# Test_Jig_Project.net
KiCad netlist of a schematic drawn in Altium Designer
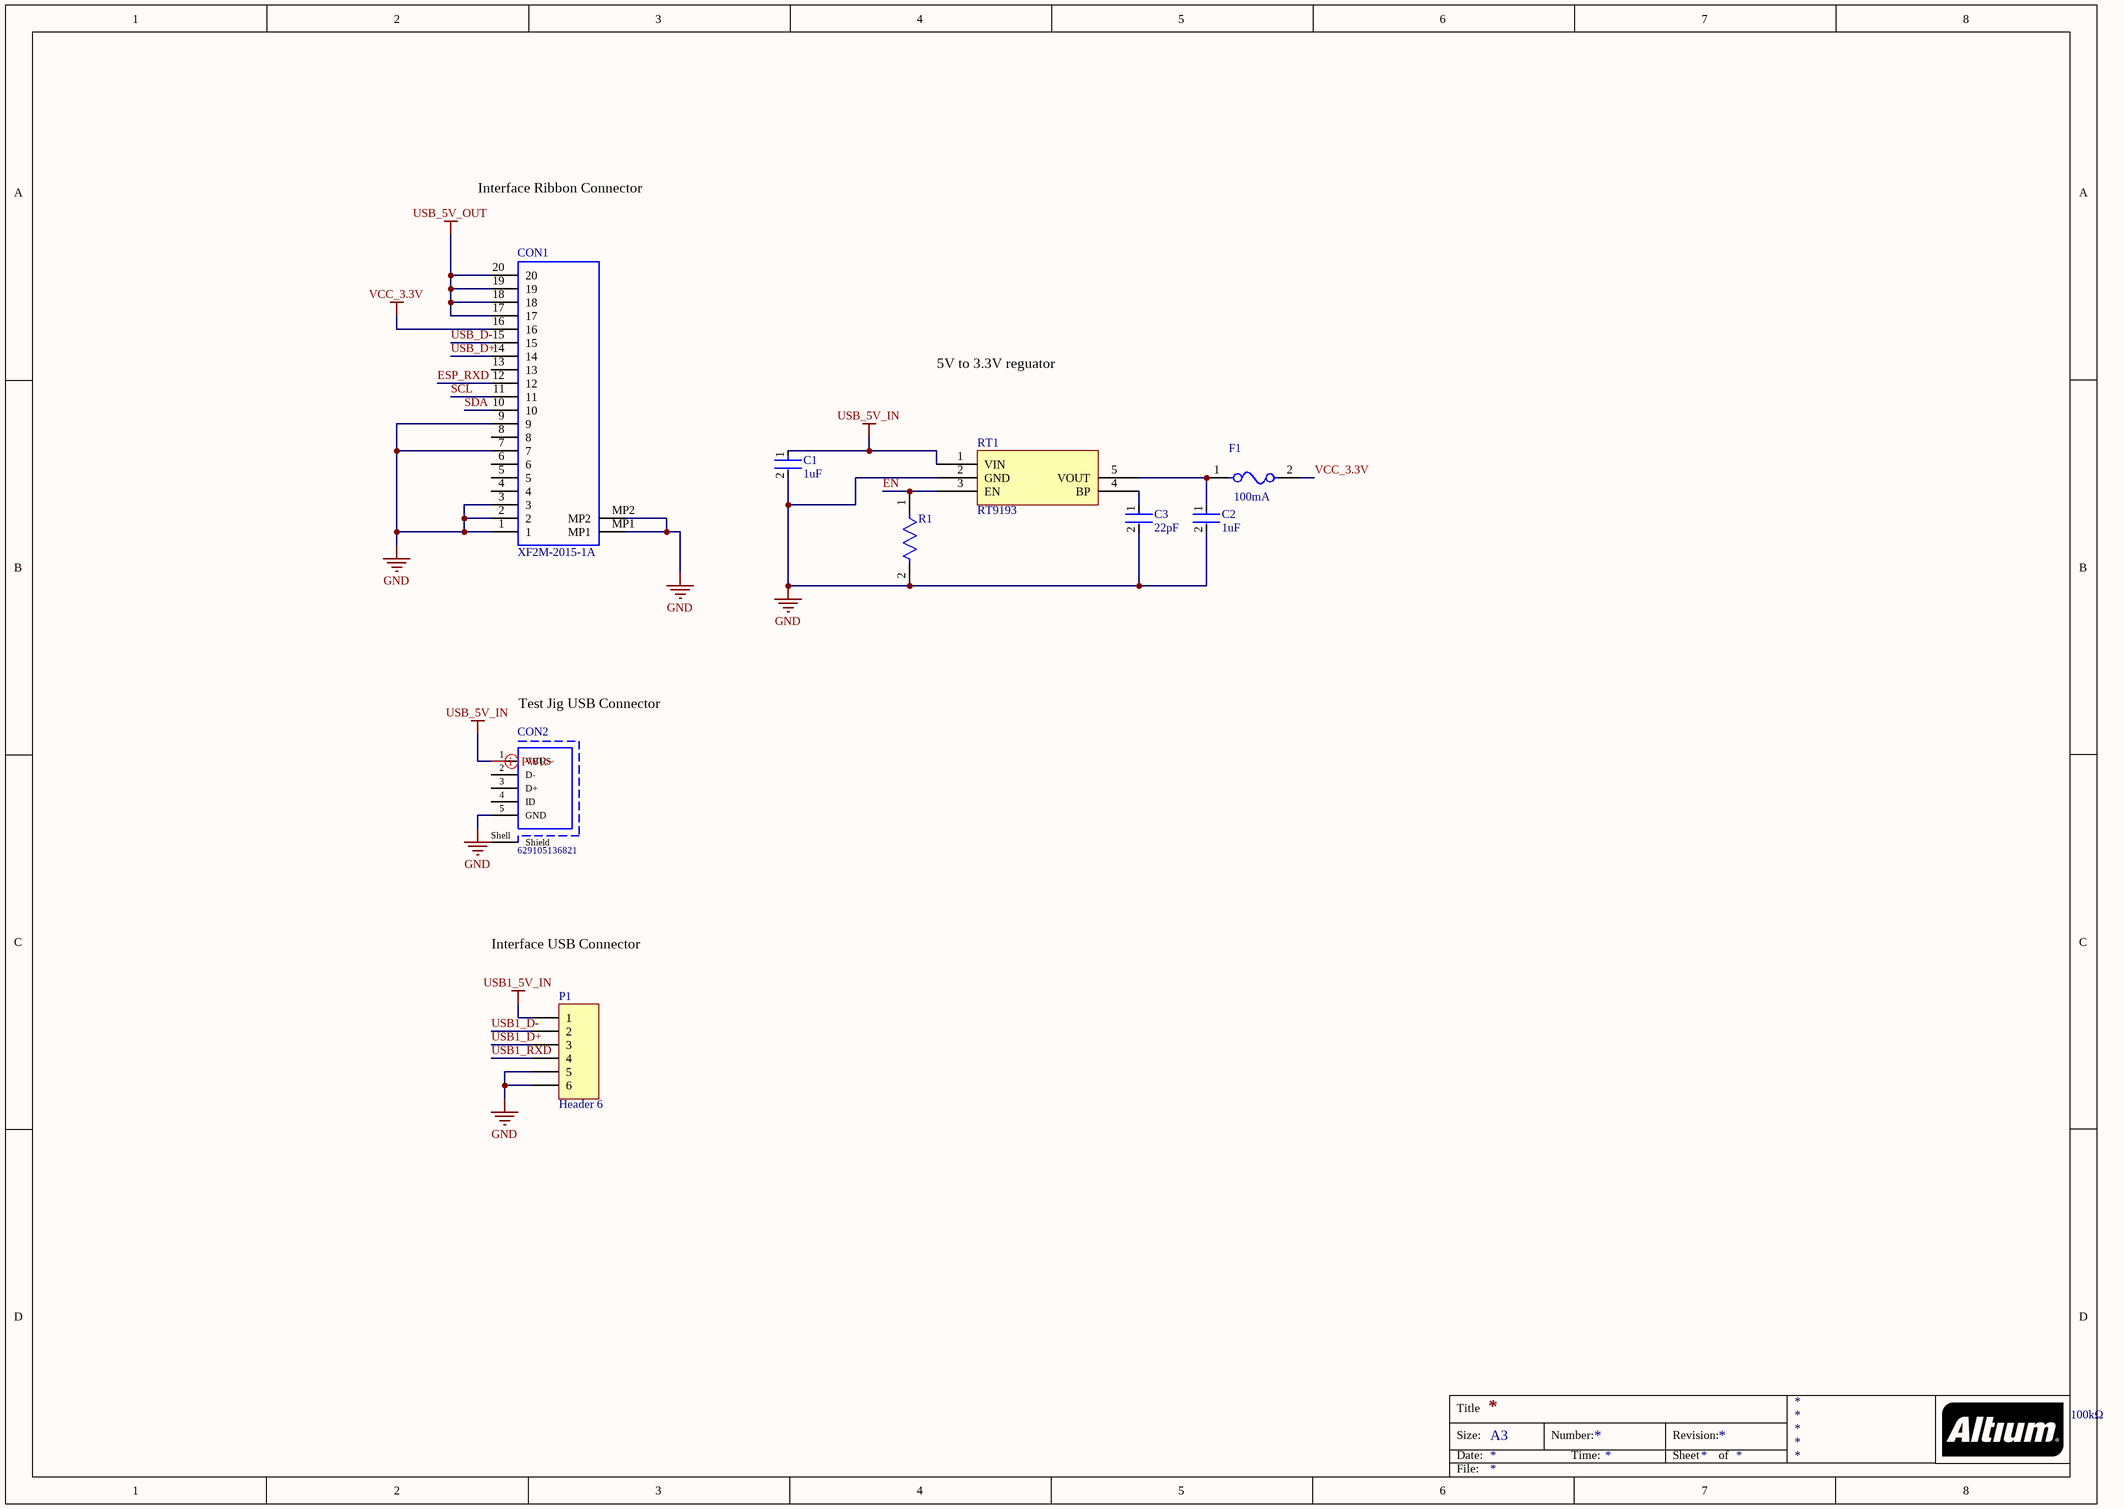
[diagram p0: Test_Jig_Project.SchDoc]

(export (version "E")
  (design (tool "Eeschema 10.0.6"))
  (components
    (comp (ref "C1")
      (value "1uF")
      (footprint "FP-CC0805-0_85-MFG")
      (description "CAP CER 1UF 10V X7R 0805")
      (fields
        (field (name "MANUFACTURER") "Yageo")
        (field (name "OCTOPART") "https://octopart.com/cc0805kkx7r6bb105-yageo-42522859")
      )
      (libsource (lib "Altium Content Vault") (part "11868f565c42a9108669ba33697ecf6"))
    )
    (comp (ref "C2")
      (value "1uF")
      (footprint "FP-CC0805-0_85-MFG")
      (description "CAP CER 1UF 10V X7R 0805")
      (fields
        (field (name "MANUFACTURER") "Yageo")
        (field (name "OCTOPART") "https://octopart.com/cc0805kkx7r6bb105-yageo-42522859")
      )
      (libsource (lib "Altium Content Vault") (part "11868f565c42a9108669ba33697ecf6"))
    )
    (comp (ref "C3")
      (value "22pF")
      (footprint "FP-C0402-BB-MFG")
      (description "CAP CER 22PF 10V NP0 0402")
      (fields (field (name "MFR. PART #") "C0402C220K8GACTU") (field (name "MANUFACTURER") "Kemet"))
      (libsource (lib "Altium Content Vault") (part "b4654b650e69147ec39a6b967a45e02"))
    )
    (comp (ref "CON1")
      (value "XF2M-2015-1A")
      (footprint "XF2M20151A")
      (fields
        (field (name "MANUFACTURER") "Omron Electronics")
        (field (name "MOUSER PART NUMBER") "653-XF2M-2015-1A")
      )
      (libsource (lib "XF2M-2015-1A") (part "XF2M-2015-1A"))
    )
    (comp (ref "CON2")
      (value "629105136821")
      (footprint "629105136821")
      (description "Micro USB 2.0 Type B Receptacle WR-COM, Horizontal, SMT, with Pads and Pegs")
      (fields
        (field (name "MANUFACTURER") "Wurth Elektronik")
        (field (name "MFR. PART #") "629105150521")
        (field (name "PUBLISHER") "WurthElektronik")
      )
      (libsource (lib "Altium Content Vault") (part "WE-USB-5-1SHLD"))
    )
    (comp (ref "F1")
      (value "100mA")
      (footprint "FP-MF-PSMF-MFG")
      (description "PTC RESET FUSE 15V 100MA 0805")
      (fields
        (field (name "OCTOPART") "https://octopart.com/mf-psmf010x-2-bourns-7483441")
        (field (name "MFR. PART #") "MF-PSMF010X-2")
      )
      (libsource (lib "Altium Content Vault") (part "5bcf9b9f640e542cf0359d10258e979"))
    )
    (comp (ref "P1")
      (value "Header 6")
      (footprint "HDR1X6")
      (description "Header, 6-Pin")
      (fields (field (name "PUBLISHER") "Altium Limited"))
      (libsource (lib "Miscellaneous Connectors") (part "Header 6"))
    )
    (comp (ref "R1")
      (value "100kΩ")
      (footprint "FP-CRCW0402-e3-IPC_C")
      (description "RES Thick Film, 100kΩ, 1%, 0.063W, 100ppm/°C, 0402")
      (fields (field (name "TOLERANCE") "1%") (field (name "MANUFACTURER") "Stackpole Electronics"))
      (libsource (lib "Altium Content Vault") (part "1029c3af85768c4190bb7ad29bc67b5"))
    )
    (comp (ref "RT1")
      (value "RT9193")
      (footprint "SOT85P279X130-5N")
      (fields (field (name "MANUFACTURER") "Richtek Tech") (field (name "MFR. PART #") "RT9193-33GB"))
      (libsource (lib "RT9193") (part "Component_1"))
    )
  )
  (nets
    (net (code "1") (name "/EN") (class "Default")
      (node (ref "R1") (pin "1") (pinfunction "1_1") (pintype "passive"))
      (node (ref "RT1") (pin "3") (pinfunction "EN_3") (pintype "power_in"))
    )
    (net (code "2") (name "/ESP_RXD") (class "Default")
      (node (ref "CON1") (pin "12") (pinfunction "12_12") (pintype "passive"))
    )
    (net (code "3") (name "/SCL") (class "Default")
      (node (ref "CON1") (pin "11") (pinfunction "11_11") (pintype "passive"))
    )
    (net (code "4") (name "/SDA") (class "Default")
      (node (ref "CON1") (pin "10") (pinfunction "10_10") (pintype "passive"))
    )
    (net (code "5") (name "/USB1_D+") (class "Default")
      (node (ref "P1") (pin "3") (pinfunction "3_3") (pintype "passive"))
    )
    (net (code "6") (name "/USB1_D-") (class "Default")
      (node (ref "P1") (pin "2") (pinfunction "2_2") (pintype "passive"))
    )
    (net (code "7") (name "/USB1_RXD") (class "Default")
      (node (ref "P1") (pin "4") (pinfunction "4_4") (pintype "passive"))
    )
    (net (code "8") (name "/USB_D+") (class "Default")
      (node (ref "CON1") (pin "14") (pinfunction "14_14") (pintype "passive"))
    )
    (net (code "9") (name "/USB_D-") (class "Default")
      (node (ref "CON1") (pin "15") (pinfunction "15_15") (pintype "passive"))
    )
    (net (code "10") (name "GND") (class "Default")
      (node (ref "C1") (pin "2") (pinfunction "2_2") (pintype "passive"))
      (node (ref "C2") (pin "2") (pinfunction "2_2") (pintype "passive"))
      (node (ref "C3") (pin "2") (pinfunction "2_2") (pintype "passive"))
      (node (ref "CON1") (pin "1") (pinfunction "1_1") (pintype "passive"))
      (node (ref "CON1") (pin "2") (pinfunction "2_2") (pintype "passive"))
      (node (ref "CON1") (pin "3") (pinfunction "3_3") (pintype "passive"))
      (node (ref "CON1") (pin "7") (pinfunction "7_7") (pintype "passive"))
      (node (ref "CON1") (pin "9") (pinfunction "9_9") (pintype "passive"))
      (node (ref "CON1") (pin "MP1") (pinfunction "MP1_MP1") (pintype "passive"))
      (node (ref "CON1") (pin "MP2") (pinfunction "MP2_MP2") (pintype "passive"))
      (node (ref "CON2") (pin "5") (pinfunction "GND_5") (pintype "passive"))
      (node (ref "P1") (pin "5") (pinfunction "5_5") (pintype "passive"))
      (node (ref "P1") (pin "6") (pinfunction "6_6") (pintype "passive"))
      (node (ref "R1") (pin "2") (pinfunction "2_2") (pintype "passive"))
      (node (ref "RT1") (pin "2") (pinfunction "GND_2") (pintype "power_in"))
    )
    (net (code "11") (name "Net-(RT1-BP)") (class "Default")
      (node (ref "C3") (pin "1") (pinfunction "1_1") (pintype "passive"))
      (node (ref "RT1") (pin "4") (pinfunction "BP_4") (pintype "power_in"))
    )
    (net (code "12") (name "Net-(RT1-VOUT)") (class "Default")
      (node (ref "C2") (pin "1") (pinfunction "1_1") (pintype "passive"))
      (node (ref "F1") (pin "1") (pinfunction "1_1") (pintype "passive"))
      (node (ref "RT1") (pin "5") (pinfunction "VOUT_5") (pintype "power_in"))
    )
    (net (code "13") (name "USB1_5V_IN") (class "Default")
      (node (ref "P1") (pin "1") (pinfunction "1_1") (pintype "passive"))
    )
    (net (code "14") (name "USB_5V_IN") (class "Default")
      (node (ref "C1") (pin "1") (pinfunction "1_1") (pintype "passive"))
      (node (ref "CON2") (pin "1") (pinfunction "VBUS_1") (pintype "passive"))
      (node (ref "RT1") (pin "1") (pinfunction "VIN_1") (pintype "power_in"))
    )
    (net (code "15") (name "USB_5V_OUT") (class "Default")
      (node (ref "CON1") (pin "17") (pinfunction "17_17") (pintype "passive"))
      (node (ref "CON1") (pin "18") (pinfunction "18_18") (pintype "passive"))
      (node (ref "CON1") (pin "19") (pinfunction "19_19") (pintype "passive"))
      (node (ref "CON1") (pin "20") (pinfunction "20_20") (pintype "passive"))
    )
    (net (code "16") (name "VCC_3.3V") (class "Default")
      (node (ref "CON1") (pin "16") (pinfunction "16_16") (pintype "passive"))
      (node (ref "F1") (pin "2") (pinfunction "2_2") (pintype "passive"))
    )
    (net (code "17") (name "unconnected-(CON1-Pad4)") (class "Default")
      (node (ref "CON1") (pin "4") (pinfunction "4_4") (pintype "passive"))
    )
    (net (code "18") (name "unconnected-(CON1-Pad5)") (class "Default")
      (node (ref "CON1") (pin "5") (pinfunction "5_5") (pintype "passive"))
    )
    (net (code "19") (name "unconnected-(CON1-Pad6)") (class "Default")
      (node (ref "CON1") (pin "6") (pinfunction "6_6") (pintype "passive"))
    )
    (net (code "20") (name "unconnected-(CON1-Pad8)") (class "Default")
      (node (ref "CON1") (pin "8") (pinfunction "8_8") (pintype "passive"))
    )
    (net (code "21") (name "unconnected-(CON1-Pad13)") (class "Default")
      (node (ref "CON1") (pin "13") (pinfunction "13_13") (pintype "passive"))
    )
    (net (code "22") (name "unconnected-(CON2-D+-Pad3)") (class "Default")
      (node (ref "CON2") (pin "3") (pinfunction "D+_3") (pintype "passive"))
    )
    (net (code "23") (name "unconnected-(CON2-D--Pad2)") (class "Default")
      (node (ref "CON2") (pin "2") (pinfunction "D-_2") (pintype "passive"))
    )
    (net (code "24") (name "unconnected-(CON2-ID-Pad4)") (class "Default")
      (node (ref "CON2") (pin "4") (pinfunction "ID_4") (pintype "passive"))
    )
    (net (code "25") (name "unconnected-(CON2-Shield-PadShell)") (class "Default")
      (node (ref "CON2") (pin "Shell") (pinfunction "Shield_Shell") (pintype "passive"))
    )
  )
)
